# interface.net
KiCad netlist of a schematic drawn in EAGLE
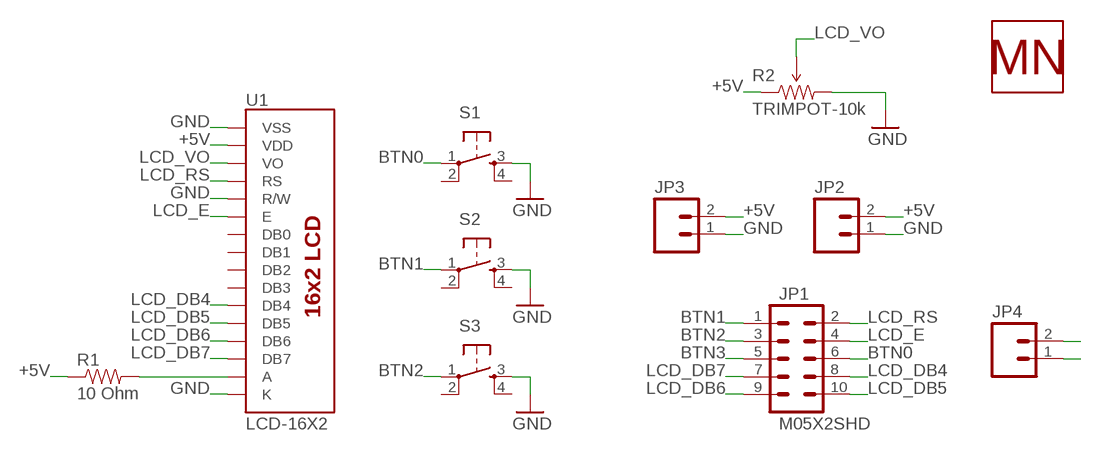
[diagram p0: schematic, sheet 1]

(export (version "E")
  (design (tool "Eeschema 10.0.6"))
  (components
    (comp (ref "JP1")
      (value "M05X2SHD")
      (footprint "eagle-import:2X5-SHROUDED")
      (libsource (lib "eagle-import") (part "M05X2SHD"))
    )
    (comp (ref "JP2")
      (value "M02POLAR")
      (footprint "eagle-import:MOLEX-1X2")
      (libsource (lib "eagle-import") (part "M02POLAR"))
    )
    (comp (ref "JP3")
      (value "M02PTH")
      (footprint "eagle-import:1X02")
      (libsource (lib "eagle-import") (part "M02PTH"))
    )
    (comp (ref "JP4")
      (value "M02PTH")
      (footprint "eagle-import:1X02")
      (libsource (lib "eagle-import") (part "M02PTH"))
    )
    (comp (ref "R1")
      (value "10 Ohm")
      (footprint "eagle-import:1206")
      (libsource (lib "eagle-import") (part "RESISTOR1206"))
    )
    (comp (ref "R2")
      (value "TRIMPOT-10k")
      (footprint "eagle-import:TRIMPOT_TC33")
      (libsource (lib "eagle-import") (part "TRIMPOT-2"))
    )
    (comp (ref "S1")
      (value "TAC_SWITCHPTH")
      (footprint "eagle-import:TACTILE-PTH")
      (libsource (lib "eagle-import") (part "TAC_SWITCHPTH"))
    )
    (comp (ref "S2")
      (value "TAC_SWITCHPTH")
      (footprint "eagle-import:TACTILE-PTH")
      (libsource (lib "eagle-import") (part "TAC_SWITCHPTH"))
    )
    (comp (ref "S3")
      (value "TAC_SWITCHPTH")
      (footprint "eagle-import:TACTILE-PTH")
      (libsource (lib "eagle-import") (part "TAC_SWITCHPTH"))
    )
    (comp (ref "U$5")
      (value "MN-LOGO")
      (footprint "eagle-import:MN-LOGO")
      (libsource (lib "eagle-import") (part "MN-LOGO"))
    )
    (comp (ref "U1")
      (value "LCD-16X2")
      (footprint "eagle-import:LCD-16X2_NOLEFTDRILL")
      (libsource (lib "eagle-import") (part "LCD-16X2"))
    )
  )
  (nets
    (net (code "1") (name "/+5V") (class "Default")
      (node (ref "JP2") (pin "2") (pinfunction "2_2") (pintype "passive"))
      (node (ref "JP3") (pin "2") (pinfunction "2_2") (pintype "passive"))
      (node (ref "R1") (pin "1") (pinfunction "1_1") (pintype "passive"))
      (node (ref "R2") (pin "1") (pinfunction "CCW_1") (pintype "passive"))
      (node (ref "U1") (pin "2") (pinfunction "VDD_2") (pintype "power_in"))
    )
    (net (code "2") (name "/BTN0") (class "Default")
      (node (ref "JP1") (pin "6") (pinfunction "6_6") (pintype "passive"))
      (node (ref "S1") (pin "1") (pinfunction "1_1") (pintype "passive"))
    )
    (net (code "3") (name "/BTN1") (class "Default")
      (node (ref "JP1") (pin "1") (pinfunction "1_1") (pintype "passive"))
      (node (ref "S2") (pin "1") (pinfunction "1_1") (pintype "passive"))
    )
    (net (code "4") (name "/BTN2") (class "Default")
      (node (ref "JP1") (pin "3") (pinfunction "3_3") (pintype "passive"))
      (node (ref "S3") (pin "1") (pinfunction "1_1") (pintype "passive"))
    )
    (net (code "5") (name "/BTN3") (class "Default")
      (node (ref "JP1") (pin "5") (pinfunction "5_5") (pintype "passive"))
      (node (ref "JP4") (pin "2") (pinfunction "2_2") (pintype "passive"))
    )
    (net (code "6") (name "/LCD_DB4") (class "Default")
      (node (ref "JP1") (pin "8") (pinfunction "8_8") (pintype "passive"))
      (node (ref "U1") (pin "11") (pinfunction "DB4_11") (pintype "bidirectional"))
    )
    (net (code "7") (name "/LCD_DB5") (class "Default")
      (node (ref "JP1") (pin "10") (pinfunction "10_10") (pintype "passive"))
      (node (ref "U1") (pin "12") (pinfunction "DB5_12") (pintype "bidirectional"))
    )
    (net (code "8") (name "/LCD_DB6") (class "Default")
      (node (ref "JP1") (pin "9") (pinfunction "9_9") (pintype "passive"))
      (node (ref "U1") (pin "13") (pinfunction "DB6_13") (pintype "bidirectional"))
    )
    (net (code "9") (name "/LCD_DB7") (class "Default")
      (node (ref "JP1") (pin "7") (pinfunction "7_7") (pintype "passive"))
      (node (ref "U1") (pin "14") (pinfunction "DB7_14") (pintype "bidirectional"))
    )
    (net (code "10") (name "/LCD_E") (class "Default")
      (node (ref "JP1") (pin "4") (pinfunction "4_4") (pintype "passive"))
      (node (ref "U1") (pin "6") (pinfunction "E_6") (pintype "input"))
    )
    (net (code "11") (name "/LCD_RS") (class "Default")
      (node (ref "JP1") (pin "2") (pinfunction "2_2") (pintype "passive"))
      (node (ref "U1") (pin "4") (pinfunction "RS_4") (pintype "input"))
    )
    (net (code "12") (name "/LCD_VO") (class "Default")
      (node (ref "R2") (pin "2") (pinfunction "WIPER_2") (pintype "passive"))
      (node (ref "U1") (pin "3") (pinfunction "VO_3") (pintype "bidirectional"))
    )
    (net (code "13") (name "GND") (class "Default")
      (node (ref "JP2") (pin "1") (pinfunction "1_1") (pintype "passive"))
      (node (ref "JP3") (pin "1") (pinfunction "1_1") (pintype "passive"))
      (node (ref "JP4") (pin "1") (pinfunction "1_1") (pintype "passive"))
      (node (ref "R2") (pin "3") (pinfunction "CW_3") (pintype "passive"))
      (node (ref "S1") (pin "3") (pinfunction "3_3") (pintype "passive"))
      (node (ref "S2") (pin "3") (pinfunction "3_3") (pintype "passive"))
      (node (ref "S3") (pin "3") (pinfunction "3_3") (pintype "passive"))
      (node (ref "U1") (pin "1") (pinfunction "VSS_1") (pintype "power_in"))
      (node (ref "U1") (pin "16") (pinfunction "K_16") (pintype "power_in"))
      (node (ref "U1") (pin "5") (pinfunction "R/W_5") (pintype "input"))
    )
    (net (code "14") (name "Net-(U1-A)") (class "Default")
      (node (ref "R1") (pin "2") (pinfunction "2_2") (pintype "passive"))
      (node (ref "U1") (pin "15") (pinfunction "A_15") (pintype "power_in"))
    )
    (net (code "15") (name "unconnected-(S1-Pad2)") (class "Default")
      (node (ref "S1") (pin "2") (pinfunction "2_2") (pintype "passive"))
    )
    (net (code "16") (name "unconnected-(S1-Pad4)") (class "Default")
      (node (ref "S1") (pin "4") (pinfunction "4_4") (pintype "passive"))
    )
    (net (code "17") (name "unconnected-(S2-Pad2)") (class "Default")
      (node (ref "S2") (pin "2") (pinfunction "2_2") (pintype "passive"))
    )
    (net (code "18") (name "unconnected-(S2-Pad4)") (class "Default")
      (node (ref "S2") (pin "4") (pinfunction "4_4") (pintype "passive"))
    )
    (net (code "19") (name "unconnected-(S3-Pad2)") (class "Default")
      (node (ref "S3") (pin "2") (pinfunction "2_2") (pintype "passive"))
    )
    (net (code "20") (name "unconnected-(S3-Pad4)") (class "Default")
      (node (ref "S3") (pin "4") (pinfunction "4_4") (pintype "passive"))
    )
    (net (code "21") (name "unconnected-(U1-DB0-Pad7)") (class "Default")
      (node (ref "U1") (pin "7") (pinfunction "DB0_7") (pintype "bidirectional"))
    )
    (net (code "22") (name "unconnected-(U1-DB1-Pad8)") (class "Default")
      (node (ref "U1") (pin "8") (pinfunction "DB1_8") (pintype "bidirectional"))
    )
    (net (code "23") (name "unconnected-(U1-DB2-Pad9)") (class "Default")
      (node (ref "U1") (pin "9") (pinfunction "DB2_9") (pintype "bidirectional"))
    )
    (net (code "24") (name "unconnected-(U1-DB3-Pad10)") (class "Default")
      (node (ref "U1") (pin "10") (pinfunction "DB3_10") (pintype "bidirectional"))
    )
  )
)
